# 08_-_FPGA_-_DDR3.net
KiCad netlist of a schematic drawn in Altium Designer
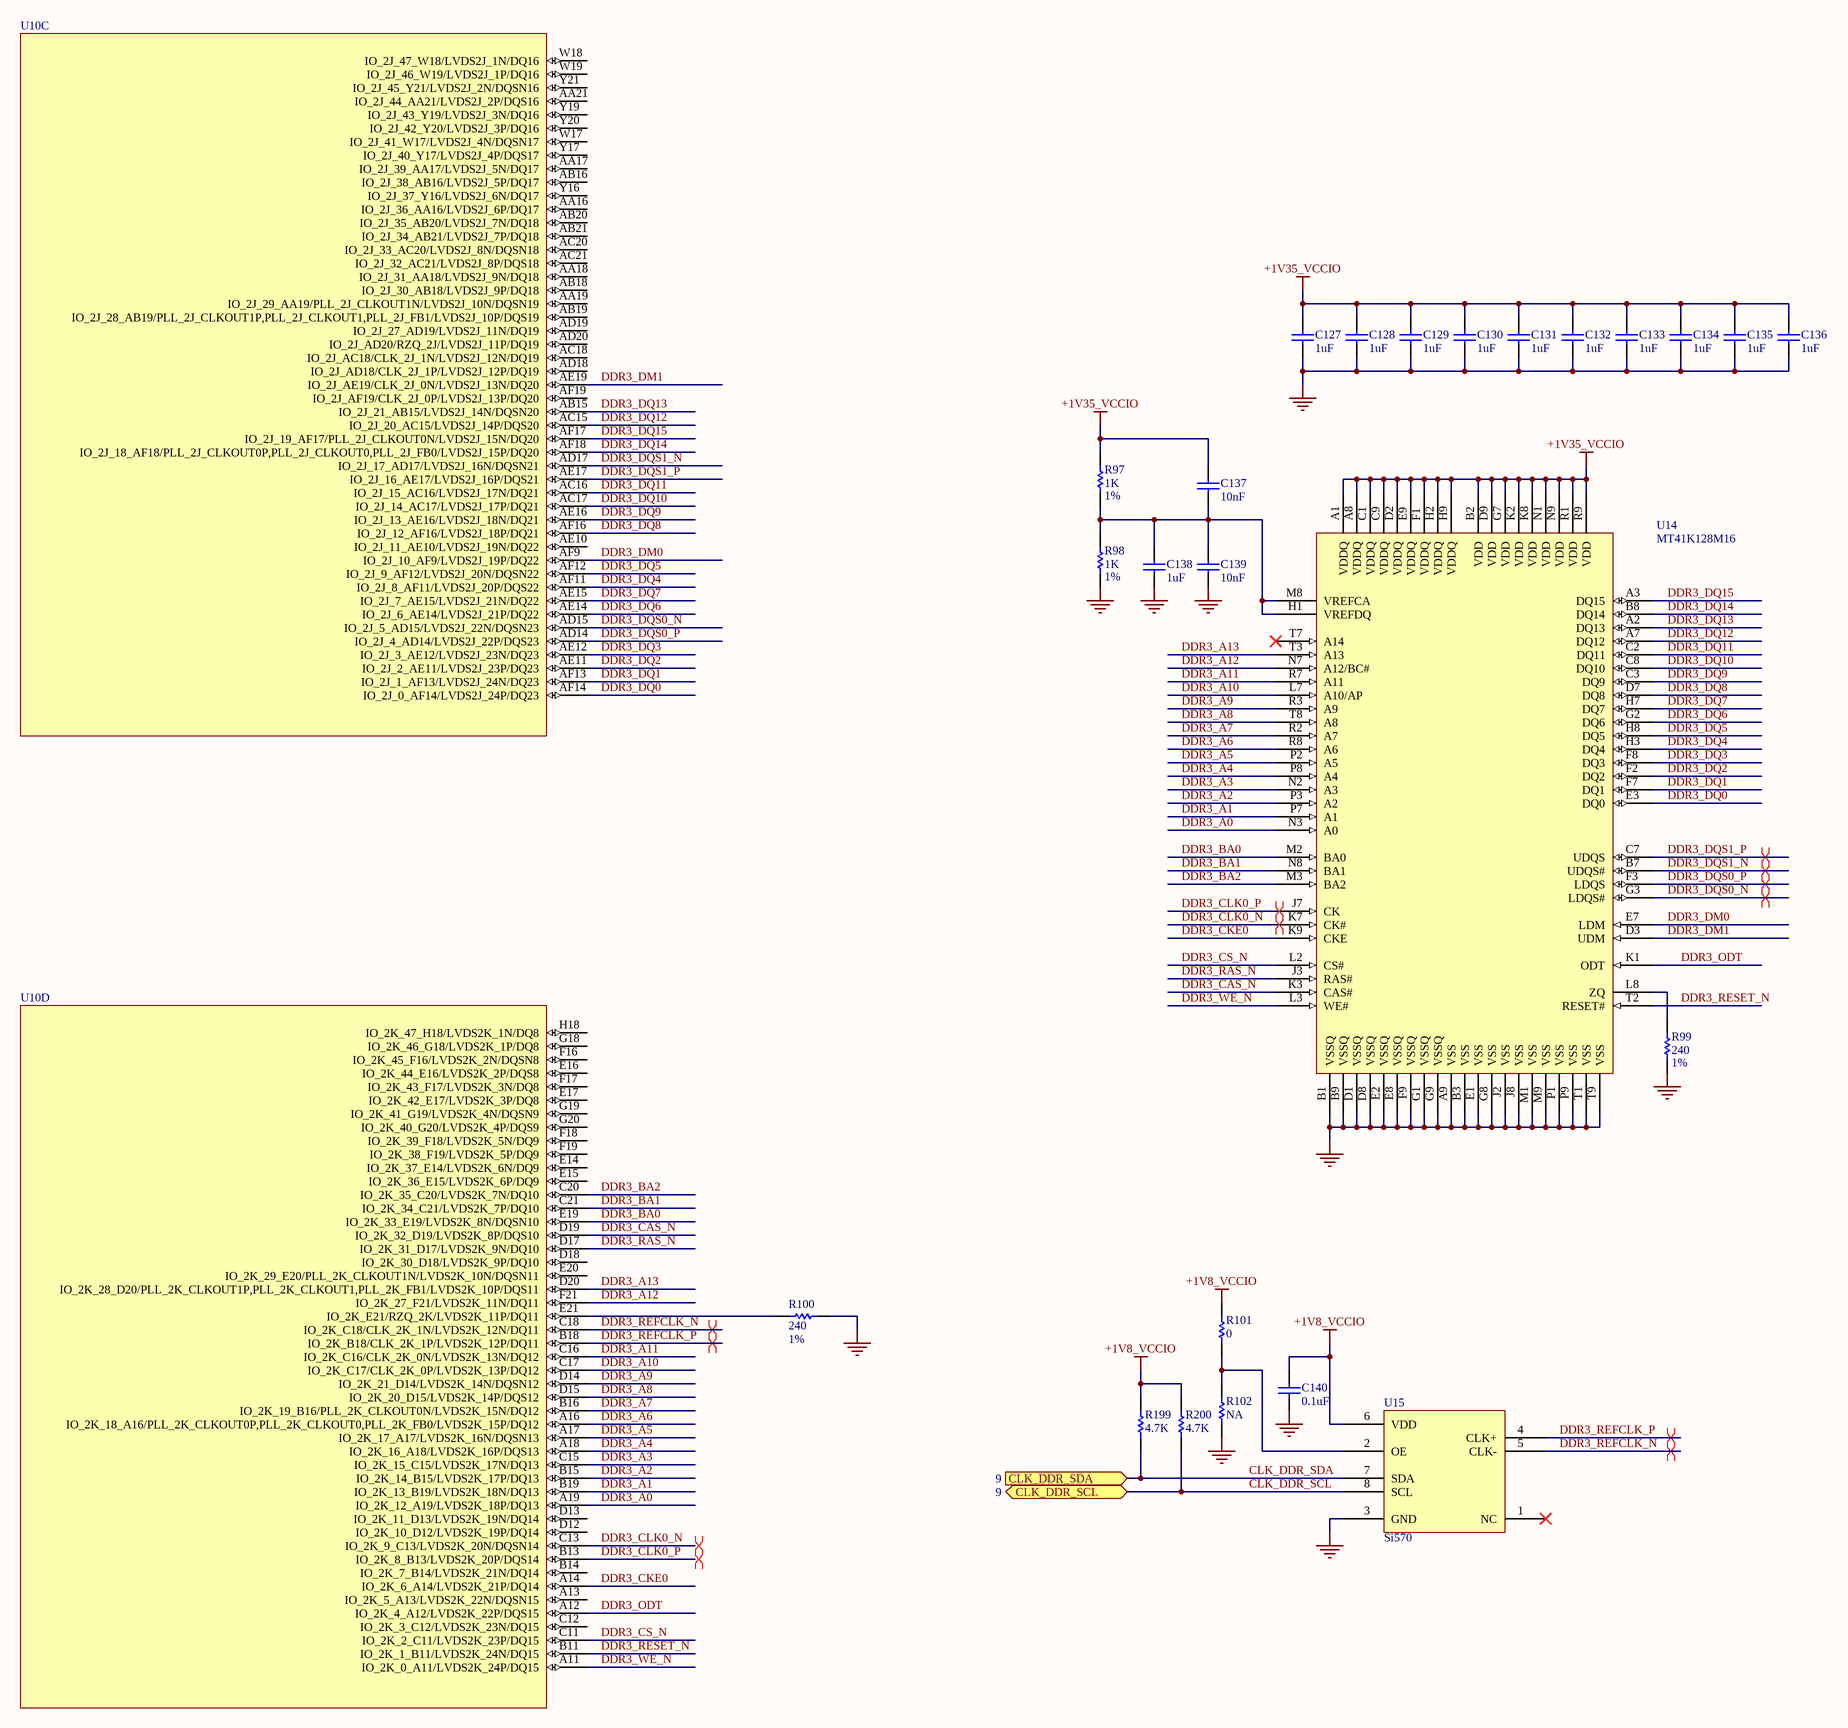
[diagram p0: [08] - FPGA - DDR3.SchDoc]

(export (version "E")
  (design (tool "Eeschema 10.0.6"))
  (components
    (comp (ref "C127")
      (value "1uF")
      (footprint "0402_C")
      (description "Non-Pol SMD Capacitor")
      (fields (field (name "MANUFACTURER PART NUM") "GRM155R70J105KA12"))
      (libsource (lib "Passive Components") (part "Cap SMD"))
    )
    (comp (ref "C128")
      (value "1uF")
      (footprint "0402_C")
      (description "Non-Pol SMD Capacitor")
      (fields (field (name "MANUFACTURER PART NUM") "GRM155R70J105KA12"))
      (libsource (lib "Passive Components") (part "Cap SMD"))
    )
    (comp (ref "C129")
      (value "1uF")
      (footprint "0402_C")
      (description "Non-Pol SMD Capacitor")
      (fields (field (name "MANUFACTURER PART NUM") "GRM155R70J105KA12"))
      (libsource (lib "Passive Components") (part "Cap SMD"))
    )
    (comp (ref "C130")
      (value "1uF")
      (footprint "0402_C")
      (description "Non-Pol SMD Capacitor")
      (fields (field (name "MANUFACTURER PART NUM") "GRM155R70J105KA12"))
      (libsource (lib "Passive Components") (part "Cap SMD"))
    )
    (comp (ref "C131")
      (value "1uF")
      (footprint "0402_C")
      (description "Non-Pol SMD Capacitor")
      (fields (field (name "MANUFACTURER PART NUM") "GRM155R70J105KA12"))
      (libsource (lib "Passive Components") (part "Cap SMD"))
    )
    (comp (ref "C132")
      (value "1uF")
      (footprint "0402_C")
      (description "Non-Pol SMD Capacitor")
      (fields (field (name "MANUFACTURER PART NUM") "GRM155R70J105KA12"))
      (libsource (lib "Passive Components") (part "Cap SMD"))
    )
    (comp (ref "C133")
      (value "1uF")
      (footprint "0402_C")
      (description "Non-Pol SMD Capacitor")
      (fields (field (name "MANUFACTURER PART NUM") "GRM155R70J105KA12"))
      (libsource (lib "Passive Components") (part "Cap SMD"))
    )
    (comp (ref "C134")
      (value "1uF")
      (footprint "0402_C")
      (description "Non-Pol SMD Capacitor")
      (fields (field (name "MANUFACTURER PART NUM") "GRM155R70J105KA12"))
      (libsource (lib "Passive Components") (part "Cap SMD"))
    )
    (comp (ref "C135")
      (value "1uF")
      (footprint "0402_C")
      (description "Non-Pol SMD Capacitor")
      (fields (field (name "MANUFACTURER PART NUM") "GRM155R70J105KA12"))
      (libsource (lib "Passive Components") (part "Cap SMD"))
    )
    (comp (ref "C136")
      (value "1uF")
      (footprint "0402_C")
      (description "Non-Pol SMD Capacitor")
      (fields (field (name "MANUFACTURER PART NUM") "GRM155R70J105KA12"))
      (libsource (lib "Passive Components") (part "Cap SMD"))
    )
    (comp (ref "C137")
      (value "10nF")
      (footprint "0402_C")
      (description "Non-Pol SMD Capacitor")
      (libsource (lib "Passive Components") (part "Cap SMD"))
    )
    (comp (ref "C138")
      (value "1uF")
      (footprint "0805_C")
      (description "Non-Pol SMD Capacitor")
      (libsource (lib "Passive Components") (part "Cap SMD"))
    )
    (comp (ref "C139")
      (value "10nF")
      (footprint "0402_C")
      (description "Non-Pol SMD Capacitor")
      (libsource (lib "Passive Components") (part "Cap SMD"))
    )
    (comp (ref "C140")
      (value "0.1uF")
      (footprint "0402_C")
      (description "Non-Pol SMD Capacitor")
      (libsource (lib "Passive Components") (part "Cap SMD"))
    )
    (comp (ref "R97")
      (value "1K")
      (footprint "0402_R")
      (description "SMD Resistor")
      (fields (field (name "TOLERANCE") "1%"))
      (libsource (lib "Passive Components") (part "Res SMD"))
    )
    (comp (ref "R98")
      (value "1K")
      (footprint "0402_R")
      (description "SMD Resistor")
      (fields (field (name "TOLERANCE") "1%"))
      (libsource (lib "Passive Components") (part "Res SMD"))
    )
    (comp (ref "R99")
      (value "240")
      (footprint "0402_R")
      (description "SMD Resistor")
      (fields (field (name "TOLERANCE") "1%"))
      (libsource (lib "Passive Components") (part "Res SMD"))
    )
    (comp (ref "R100")
      (value "240")
      (footprint "0402_R")
      (description "SMD Resistor")
      (fields (field (name "TOLERANCE") "1%"))
      (libsource (lib "Passive Components") (part "Res SMD"))
    )
    (comp (ref "R101")
      (value "0")
      (footprint "0402_R")
      (description "SMD Resistor")
      (fields (field (name "TOLERANCE") "5%"))
      (libsource (lib "Passive Components") (part "Res SMD"))
    )
    (comp (ref "R102")
      (value "NA")
      (footprint "0402_R")
      (description "SMD Resistor")
      (fields (field (name "TOLERANCE") "5%"))
      (libsource (lib "Passive Components") (part "Res SMD"))
    )
    (comp (ref "R199")
      (value "4.7K")
      (footprint "0402_R")
      (description "SMD Resistor")
      (fields (field (name "TOLERANCE") "5%"))
      (libsource (lib "Passive Components") (part "Res SMD"))
    )
    (comp (ref "R200")
      (value "4.7K")
      (footprint "0402_R")
      (description "SMD Resistor")
      (fields (field (name "TOLERANCE") "5%"))
      (libsource (lib "Passive Components") (part "Res SMD"))
    )
    (comp (ref "U10") (value "10AX016 F27") (footprint "FBGA672") (libsource (lib "") (part "10AX016_1")))
    (comp (ref "U14")
      (value "MT41K128M16")
      (footprint "FBGA96")
      (description "2Gb: x16 DDR3 SDRAM")
      (fields (field (name "MANUFACTURER PART NUM") "MT41K128M16JT-125"))
      (libsource (lib "Project_schlib") (part "MT41K128M16JT"))
    )
    (comp (ref "U15")
      (value "Si570")
      (description "10 MHZ TO 1.4 GHZ I2C PROGRAMMABLE XO/VCXO")
      (libsource (lib "Project_schlib") (part "Si570"))
    )
  )
  (nets
    (net (code "1") (name "+1V8_VCCIO") (class "Default")
      (node (ref "C140") (pin "1") (pinfunction "1_1") (pintype "passive"))
      (node (ref "R101") (pin "2") (pinfunction "2_2") (pintype "passive"))
      (node (ref "R199") (pin "2") (pinfunction "2_2") (pintype "passive"))
      (node (ref "R200") (pin "2") (pinfunction "2_2") (pintype "passive"))
      (node (ref "U15") (pin "6") (pinfunction "VDD_6") (pintype "power_in"))
    )
    (net (code "2") (name "+1V35_VCCIO") (class "Default")
      (node (ref "C127") (pin "2") (pinfunction "2_2") (pintype "passive"))
      (node (ref "C128") (pin "2") (pinfunction "2_2") (pintype "passive"))
      (node (ref "C129") (pin "2") (pinfunction "2_2") (pintype "passive"))
      (node (ref "C130") (pin "2") (pinfunction "2_2") (pintype "passive"))
      (node (ref "C131") (pin "2") (pinfunction "2_2") (pintype "passive"))
      (node (ref "C132") (pin "2") (pinfunction "2_2") (pintype "passive"))
      (node (ref "C133") (pin "2") (pinfunction "2_2") (pintype "passive"))
      (node (ref "C134") (pin "2") (pinfunction "2_2") (pintype "passive"))
      (node (ref "C135") (pin "2") (pinfunction "2_2") (pintype "passive"))
      (node (ref "C136") (pin "2") (pinfunction "2_2") (pintype "passive"))
      (node (ref "C137") (pin "2") (pinfunction "2_2") (pintype "passive"))
      (node (ref "R97") (pin "2") (pinfunction "2_2") (pintype "passive"))
      (node (ref "U14") (pin "A1") (pinfunction "VDDQ_A1") (pintype "power_in"))
      (node (ref "U14") (pin "A8") (pinfunction "VDDQ_A8") (pintype "power_in"))
      (node (ref "U14") (pin "B2") (pinfunction "VDD_B2") (pintype "power_in"))
      (node (ref "U14") (pin "C1") (pinfunction "VDDQ_C1") (pintype "power_in"))
      (node (ref "U14") (pin "C9") (pinfunction "VDDQ_C9") (pintype "power_in"))
      (node (ref "U14") (pin "D2") (pinfunction "VDDQ_D2") (pintype "power_in"))
      (node (ref "U14") (pin "D9") (pinfunction "VDD_D9") (pintype "power_in"))
      (node (ref "U14") (pin "E9") (pinfunction "VDDQ_E9") (pintype "power_in"))
      (node (ref "U14") (pin "F1") (pinfunction "VDDQ_F1") (pintype "power_in"))
      (node (ref "U14") (pin "G7") (pinfunction "VDD_G7") (pintype "power_in"))
      (node (ref "U14") (pin "H2") (pinfunction "VDDQ_H2") (pintype "power_in"))
      (node (ref "U14") (pin "H9") (pinfunction "VDDQ_H9") (pintype "power_in"))
      (node (ref "U14") (pin "K2") (pinfunction "VDD_K2") (pintype "power_in"))
      (node (ref "U14") (pin "K8") (pinfunction "VDD_K8") (pintype "power_in"))
      (node (ref "U14") (pin "N1") (pinfunction "VDD_N1") (pintype "power_in"))
      (node (ref "U14") (pin "N9") (pinfunction "VDD_N9") (pintype "power_in"))
      (node (ref "U14") (pin "R1") (pinfunction "VDD_R1") (pintype "power_in"))
      (node (ref "U14") (pin "R9") (pinfunction "VDD_R9") (pintype "power_in"))
    )
    (net (code "3") (name "/CLK_DDR_SCL") (class "Default")
      (node (ref "R200") (pin "1") (pinfunction "1_1") (pintype "passive"))
      (node (ref "U15") (pin "8") (pinfunction "SCL_8") (pintype "passive"))
    )
    (net (code "4") (name "/CLK_DDR_SDA") (class "Default")
      (node (ref "R199") (pin "1") (pinfunction "1_1") (pintype "passive"))
      (node (ref "U15") (pin "7") (pinfunction "SDA_7") (pintype "passive"))
    )
    (net (code "5") (name "/DDR3_A0") (class "Default")
      (node (ref "U10") (pin "A19") (pinfunction "IO_2K_12_A19/LVDS2K_18P/DQ13_A19") (pintype "bidirectional"))
      (node (ref "U14") (pin "N3") (pinfunction "A0_N3") (pintype "input"))
    )
    (net (code "6") (name "/DDR3_A1") (class "Default")
      (node (ref "U10") (pin "B19") (pinfunction "IO_2K_13_B19/LVDS2K_18N/DQ13_B19") (pintype "bidirectional"))
      (node (ref "U14") (pin "P7") (pinfunction "A1_P7") (pintype "input"))
    )
    (net (code "7") (name "/DDR3_A2") (class "Default")
      (node (ref "U10") (pin "B15") (pinfunction "IO_2K_14_B15/LVDS2K_17P/DQ13_B15") (pintype "bidirectional"))
      (node (ref "U14") (pin "P3") (pinfunction "A2_P3") (pintype "input"))
    )
    (net (code "8") (name "/DDR3_A3") (class "Default")
      (node (ref "U10") (pin "C15") (pinfunction "IO_2K_15_C15/LVDS2K_17N/DQ13_C15") (pintype "bidirectional"))
      (node (ref "U14") (pin "N2") (pinfunction "A3_N2") (pintype "input"))
    )
    (net (code "9") (name "/DDR3_A4") (class "Default")
      (node (ref "U10") (pin "A18") (pinfunction "IO_2K_16_A18/LVDS2K_16P/DQS13_A18") (pintype "bidirectional"))
      (node (ref "U14") (pin "P8") (pinfunction "A4_P8") (pintype "input"))
    )
    (net (code "10") (name "/DDR3_A5") (class "Default")
      (node (ref "U10") (pin "A17") (pinfunction "IO_2K_17_A17/LVDS2K_16N/DQSN13_A17") (pintype "bidirectional"))
      (node (ref "U14") (pin "P2") (pinfunction "A5_P2") (pintype "input"))
    )
    (net (code "11") (name "/DDR3_A6") (class "Default")
      (node (ref "U10") (pin "A16") (pinfunction "IO_2K_18_A16/PLL_2K_CLKOUT0P,PLL_2K_CLKOUT0,PLL_2K_FB0/LVDS2K_15P/DQ12_A16") (pintype "bidirectional"))
      (node (ref "U14") (pin "R8") (pinfunction "A6_R8") (pintype "input"))
    )
    (net (code "12") (name "/DDR3_A7") (class "Default")
      (node (ref "U10") (pin "B16") (pinfunction "IO_2K_19_B16/PLL_2K_CLKOUT0N/LVDS2K_15N/DQ12_B16") (pintype "bidirectional"))
      (node (ref "U14") (pin "R2") (pinfunction "A7_R2") (pintype "input"))
    )
    (net (code "13") (name "/DDR3_A8") (class "Default")
      (node (ref "U10") (pin "D15") (pinfunction "IO_2K_20_D15/LVDS2K_14P/DQS12_D15") (pintype "bidirectional"))
      (node (ref "U14") (pin "T8") (pinfunction "A8_T8") (pintype "input"))
    )
    (net (code "14") (name "/DDR3_A9") (class "Default")
      (node (ref "U10") (pin "D14") (pinfunction "IO_2K_21_D14/LVDS2K_14N/DQSN12_D14") (pintype "bidirectional"))
      (node (ref "U14") (pin "R3") (pinfunction "A9_R3") (pintype "input"))
    )
    (net (code "15") (name "/DDR3_A10") (class "Default")
      (node (ref "U10") (pin "C17") (pinfunction "IO_2K_C17/CLK_2K_0P/LVDS2K_13P/DQ12_C17") (pintype "bidirectional"))
      (node (ref "U14") (pin "L7") (pinfunction "A10/AP_L7") (pintype "input"))
    )
    (net (code "16") (name "/DDR3_A11") (class "Default")
      (node (ref "U10") (pin "C16") (pinfunction "IO_2K_C16/CLK_2K_0N/LVDS2K_13N/DQ12_C16") (pintype "bidirectional"))
      (node (ref "U14") (pin "R7") (pinfunction "A11_R7") (pintype "input"))
    )
    (net (code "17") (name "/DDR3_A12") (class "Default")
      (node (ref "U10") (pin "F21") (pinfunction "IO_2K_27_F21/LVDS2K_11N/DQ11_F21") (pintype "bidirectional"))
      (node (ref "U14") (pin "N7") (pinfunction "A12/BC#_N7") (pintype "input"))
    )
    (net (code "18") (name "/DDR3_A13") (class "Default")
      (node (ref "U10") (pin "D20") (pinfunction "IO_2K_28_D20/PLL_2K_CLKOUT1P,PLL_2K_CLKOUT1,PLL_2K_FB1/LVDS2K_10P/DQS11_D20") (pintype "bidirectional"))
      (node (ref "U14") (pin "T3") (pinfunction "A13_T3") (pintype "input"))
    )
    (net (code "19") (name "/DDR3_BA0") (class "Default")
      (node (ref "U10") (pin "E19") (pinfunction "IO_2K_33_E19/LVDS2K_8N/DQSN10_E19") (pintype "bidirectional"))
      (node (ref "U14") (pin "M2") (pinfunction "BA0_M2") (pintype "input"))
    )
    (net (code "20") (name "/DDR3_BA1") (class "Default")
      (node (ref "U10") (pin "C21") (pinfunction "IO_2K_34_C21/LVDS2K_7P/DQ10_C21") (pintype "bidirectional"))
      (node (ref "U14") (pin "N8") (pinfunction "BA1_N8") (pintype "input"))
    )
    (net (code "21") (name "/DDR3_BA2") (class "Default")
      (node (ref "U10") (pin "C20") (pinfunction "IO_2K_35_C20/LVDS2K_7N/DQ10_C20") (pintype "bidirectional"))
      (node (ref "U14") (pin "M3") (pinfunction "BA2_M3") (pintype "input"))
    )
    (net (code "22") (name "/DDR3_CAS_N") (class "Default")
      (node (ref "U10") (pin "D19") (pinfunction "IO_2K_32_D19/LVDS2K_8P/DQS10_D19") (pintype "bidirectional"))
      (node (ref "U14") (pin "K3") (pinfunction "CAS#_K3") (pintype "input"))
    )
    (net (code "23") (name "/DDR3_CKE0") (class "Default")
      (node (ref "U10") (pin "A14") (pinfunction "IO_2K_6_A14/LVDS2K_21P/DQ14_A14") (pintype "bidirectional"))
      (node (ref "U14") (pin "K9") (pinfunction "CKE_K9") (pintype "input"))
    )
    (net (code "24") (name "/DDR3_CLK0_N") (class "Default")
      (node (ref "U10") (pin "C13") (pinfunction "IO_2K_9_C13/LVDS2K_20N/DQSN14_C13") (pintype "bidirectional"))
      (node (ref "U14") (pin "K7") (pinfunction "CK#_K7") (pintype "input"))
    )
    (net (code "25") (name "/DDR3_CLK0_P") (class "Default")
      (node (ref "U10") (pin "B13") (pinfunction "IO_2K_8_B13/LVDS2K_20P/DQS14_B13") (pintype "bidirectional"))
      (node (ref "U14") (pin "J7") (pinfunction "CK_J7") (pintype "input"))
    )
    (net (code "26") (name "/DDR3_CS_N") (class "Default")
      (node (ref "U10") (pin "C11") (pinfunction "IO_2K_2_C11/LVDS2K_23P/DQ15_C11") (pintype "bidirectional"))
      (node (ref "U14") (pin "L2") (pinfunction "CS#_L2") (pintype "input"))
    )
    (net (code "27") (name "/DDR3_DM0") (class "Default")
      (node (ref "U10") (pin "AF9") (pinfunction "IO_2J_10_AF9/LVDS2J_19P/DQ22_AF9") (pintype "bidirectional"))
      (node (ref "U14") (pin "E7") (pinfunction "LDM_E7") (pintype "input"))
    )
    (net (code "28") (name "/DDR3_DM1") (class "Default")
      (node (ref "U10") (pin "AE19") (pinfunction "IO_2J_AE19/CLK_2J_0N/LVDS2J_13N/DQ20_AE19") (pintype "bidirectional"))
      (node (ref "U14") (pin "D3") (pinfunction "UDM_D3") (pintype "input"))
    )
    (net (code "29") (name "/DDR3_DQ0") (class "Default")
      (node (ref "U10") (pin "AF14") (pinfunction "IO_2J_0_AF14/LVDS2J_24P/DQ23_AF14") (pintype "bidirectional"))
      (node (ref "U14") (pin "E3") (pinfunction "DQ0_E3") (pintype "bidirectional"))
    )
    (net (code "30") (name "/DDR3_DQ1") (class "Default")
      (node (ref "U10") (pin "AF13") (pinfunction "IO_2J_1_AF13/LVDS2J_24N/DQ23_AF13") (pintype "bidirectional"))
      (node (ref "U14") (pin "F7") (pinfunction "DQ1_F7") (pintype "bidirectional"))
    )
    (net (code "31") (name "/DDR3_DQ2") (class "Default")
      (node (ref "U10") (pin "AE11") (pinfunction "IO_2J_2_AE11/LVDS2J_23P/DQ23_AE11") (pintype "bidirectional"))
      (node (ref "U14") (pin "F2") (pinfunction "DQ2_F2") (pintype "bidirectional"))
    )
    (net (code "32") (name "/DDR3_DQ3") (class "Default")
      (node (ref "U10") (pin "AE12") (pinfunction "IO_2J_3_AE12/LVDS2J_23N/DQ23_AE12") (pintype "bidirectional"))
      (node (ref "U14") (pin "F8") (pinfunction "DQ3_F8") (pintype "bidirectional"))
    )
    (net (code "33") (name "/DDR3_DQ4") (class "Default")
      (node (ref "U10") (pin "AF11") (pinfunction "IO_2J_8_AF11/LVDS2J_20P/DQS22_AF11") (pintype "bidirectional"))
      (node (ref "U14") (pin "H3") (pinfunction "DQ4_H3") (pintype "bidirectional"))
    )
    (net (code "34") (name "/DDR3_DQ5") (class "Default")
      (node (ref "U10") (pin "AF12") (pinfunction "IO_2J_9_AF12/LVDS2J_20N/DQSN22_AF12") (pintype "bidirectional"))
      (node (ref "U14") (pin "H8") (pinfunction "DQ5_H8") (pintype "bidirectional"))
    )
    (net (code "35") (name "/DDR3_DQ6") (class "Default")
      (node (ref "U10") (pin "AE14") (pinfunction "IO_2J_6_AE14/LVDS2J_21P/DQ22_AE14") (pintype "bidirectional"))
      (node (ref "U14") (pin "G2") (pinfunction "DQ6_G2") (pintype "bidirectional"))
    )
    (net (code "36") (name "/DDR3_DQ7") (class "Default")
      (node (ref "U10") (pin "AE15") (pinfunction "IO_2J_7_AE15/LVDS2J_21N/DQ22_AE15") (pintype "bidirectional"))
      (node (ref "U14") (pin "H7") (pinfunction "DQ7_H7") (pintype "bidirectional"))
    )
    (net (code "37") (name "/DDR3_DQ8") (class "Default")
      (node (ref "U10") (pin "AF16") (pinfunction "IO_2J_12_AF16/LVDS2J_18P/DQ21_AF16") (pintype "bidirectional"))
      (node (ref "U14") (pin "D7") (pinfunction "DQ8_D7") (pintype "bidirectional"))
    )
    (net (code "38") (name "/DDR3_DQ9") (class "Default")
      (node (ref "U10") (pin "AE16") (pinfunction "IO_2J_13_AE16/LVDS2J_18N/DQ21_AE16") (pintype "bidirectional"))
      (node (ref "U14") (pin "C3") (pinfunction "DQ9_C3") (pintype "bidirectional"))
    )
    (net (code "39") (name "/DDR3_DQ10") (class "Default")
      (node (ref "U10") (pin "AC17") (pinfunction "IO_2J_14_AC17/LVDS2J_17P/DQ21_AC17") (pintype "bidirectional"))
      (node (ref "U14") (pin "C8") (pinfunction "DQ10_C8") (pintype "bidirectional"))
    )
    (net (code "40") (name "/DDR3_DQ11") (class "Default")
      (node (ref "U10") (pin "AC16") (pinfunction "IO_2J_15_AC16/LVDS2J_17N/DQ21_AC16") (pintype "bidirectional"))
      (node (ref "U14") (pin "C2") (pinfunction "DQ11_C2") (pintype "bidirectional"))
    )
    (net (code "41") (name "/DDR3_DQ12") (class "Default")
      (node (ref "U10") (pin "AC15") (pinfunction "IO_2J_20_AC15/LVDS2J_14P/DQS20_AC15") (pintype "bidirectional"))
      (node (ref "U14") (pin "A7") (pinfunction "DQ12_A7") (pintype "bidirectional"))
    )
    (net (code "42") (name "/DDR3_DQ13") (class "Default")
      (node (ref "U10") (pin "AB15") (pinfunction "IO_2J_21_AB15/LVDS2J_14N/DQSN20_AB15") (pintype "bidirectional"))
      (node (ref "U14") (pin "A2") (pinfunction "DQ13_A2") (pintype "bidirectional"))
    )
    (net (code "43") (name "/DDR3_DQ14") (class "Default")
      (node (ref "U10") (pin "AF18") (pinfunction "IO_2J_18_AF18/PLL_2J_CLKOUT0P,PLL_2J_CLKOUT0,PLL_2J_FB0/LVDS2J_15P/DQ20_AF18") (pintype "bidirectional"))
      (node (ref "U14") (pin "B8") (pinfunction "DQ14_B8") (pintype "bidirectional"))
    )
    (net (code "44") (name "/DDR3_DQ15") (class "Default")
      (node (ref "U10") (pin "AF17") (pinfunction "IO_2J_19_AF17/PLL_2J_CLKOUT0N/LVDS2J_15N/DQ20_AF17") (pintype "bidirectional"))
      (node (ref "U14") (pin "A3") (pinfunction "DQ15_A3") (pintype "bidirectional"))
    )
    (net (code "45") (name "/DDR3_DQS0_N") (class "Default")
      (node (ref "U10") (pin "AD15") (pinfunction "IO_2J_5_AD15/LVDS2J_22N/DQSN23_AD15") (pintype "bidirectional"))
      (node (ref "U14") (pin "G3") (pinfunction "LDQS#_G3") (pintype "bidirectional"))
    )
    (net (code "46") (name "/DDR3_DQS0_P") (class "Default")
      (node (ref "U10") (pin "AD14") (pinfunction "IO_2J_4_AD14/LVDS2J_22P/DQS23_AD14") (pintype "bidirectional"))
      (node (ref "U14") (pin "F3") (pinfunction "LDQS_F3") (pintype "bidirectional"))
    )
    (net (code "47") (name "/DDR3_DQS1_N") (class "Default")
      (node (ref "U10") (pin "AD17") (pinfunction "IO_2J_17_AD17/LVDS2J_16N/DQSN21_AD17") (pintype "bidirectional"))
      (node (ref "U14") (pin "B7") (pinfunction "UDQS#_B7") (pintype "bidirectional"))
    )
    (net (code "48") (name "/DDR3_DQS1_P") (class "Default")
      (node (ref "U10") (pin "AE17") (pinfunction "IO_2J_16_AE17/LVDS2J_16P/DQS21_AE17") (pintype "bidirectional"))
      (node (ref "U14") (pin "C7") (pinfunction "UDQS_C7") (pintype "bidirectional"))
    )
    (net (code "49") (name "/DDR3_ODT") (class "Default")
      (node (ref "U10") (pin "A12") (pinfunction "IO_2K_4_A12/LVDS2K_22P/DQS15_A12") (pintype "bidirectional"))
      (node (ref "U14") (pin "K1") (pinfunction "ODT_K1") (pintype "input"))
    )
    (net (code "50") (name "/DDR3_RAS_N") (class "Default")
      (node (ref "U10") (pin "D17") (pinfunction "IO_2K_31_D17/LVDS2K_9N/DQ10_D17") (pintype "bidirectional"))
      (node (ref "U14") (pin "J3") (pinfunction "RAS#_J3") (pintype "input"))
    )
    (net (code "51") (name "/DDR3_REFCLK_N") (class "Default")
      (node (ref "U10") (pin "C18") (pinfunction "IO_2K_C18/CLK_2K_1N/LVDS2K_12N/DQ11_C18") (pintype "bidirectional"))
      (node (ref "U15") (pin "5") (pinfunction "CLK-_5") (pintype "passive"))
    )
    (net (code "52") (name "/DDR3_REFCLK_P") (class "Default")
      (node (ref "U10") (pin "B18") (pinfunction "IO_2K_B18/CLK_2K_1P/LVDS2K_12P/DQ11_B18") (pintype "bidirectional"))
      (node (ref "U15") (pin "4") (pinfunction "CLK+_4") (pintype "passive"))
    )
    (net (code "53") (name "/DDR3_RESET_N") (class "Default")
      (node (ref "U10") (pin "B11") (pinfunction "IO_2K_1_B11/LVDS2K_24N/DQ15_B11") (pintype "bidirectional"))
      (node (ref "U14") (pin "T2") (pinfunction "RESET#_T2") (pintype "input"))
    )
    (net (code "54") (name "/DDR3_WE_N") (class "Default")
      (node (ref "U10") (pin "A11") (pinfunction "IO_2K_0_A11/LVDS2K_24P/DQ15_A11") (pintype "bidirectional"))
      (node (ref "U14") (pin "L3") (pinfunction "WE#_L3") (pintype "input"))
    )
    (net (code "55") (name "GND") (class "Default")
      (node (ref "C127") (pin "1") (pinfunction "1_1") (pintype "passive"))
      (node (ref "C128") (pin "1") (pinfunction "1_1") (pintype "passive"))
      (node (ref "C129") (pin "1") (pinfunction "1_1") (pintype "passive"))
      (node (ref "C130") (pin "1") (pinfunction "1_1") (pintype "passive"))
      (node (ref "C131") (pin "1") (pinfunction "1_1") (pintype "passive"))
      (node (ref "C132") (pin "1") (pinfunction "1_1") (pintype "passive"))
      (node (ref "C133") (pin "1") (pinfunction "1_1") (pintype "passive"))
      (node (ref "C134") (pin "1") (pinfunction "1_1") (pintype "passive"))
      (node (ref "C135") (pin "1") (pinfunction "1_1") (pintype "passive"))
      (node (ref "C136") (pin "1") (pinfunction "1_1") (pintype "passive"))
      (node (ref "C138") (pin "1") (pinfunction "1_1") (pintype "passive"))
      (node (ref "C139") (pin "1") (pinfunction "1_1") (pintype "passive"))
      (node (ref "C140") (pin "2") (pinfunction "2_2") (pintype "passive"))
      (node (ref "R100") (pin "1") (pinfunction "1_1") (pintype "passive"))
      (node (ref "R102") (pin "1") (pinfunction "1_1") (pintype "passive"))
      (node (ref "R98") (pin "1") (pinfunction "1_1") (pintype "passive"))
      (node (ref "R99") (pin "1") (pinfunction "1_1") (pintype "passive"))
      (node (ref "U14") (pin "A9") (pinfunction "VSS_A9") (pintype "power_in"))
      (node (ref "U14") (pin "B1") (pinfunction "VSSQ_B1") (pintype "power_in"))
      (node (ref "U14") (pin "B3") (pinfunction "VSS_B3") (pintype "power_in"))
      (node (ref "U14") (pin "B9") (pinfunction "VSSQ_B9") (pintype "power_in"))
      (node (ref "U14") (pin "D1") (pinfunction "VSSQ_D1") (pintype "power_in"))
      (node (ref "U14") (pin "D8") (pinfunction "VSSQ_D8") (pintype "power_in"))
      (node (ref "U14") (pin "E1") (pinfunction "VSS_E1") (pintype "power_in"))
      (node (ref "U14") (pin "E2") (pinfunction "VSSQ_E2") (pintype "power_in"))
      (node (ref "U14") (pin "E8") (pinfunction "VSSQ_E8") (pintype "power_in"))
      (node (ref "U14") (pin "F9") (pinfunction "VSSQ_F9") (pintype "power_in"))
      (node (ref "U14") (pin "G1") (pinfunction "VSSQ_G1") (pintype "power_in"))
      (node (ref "U14") (pin "G8") (pinfunction "VSS_G8") (pintype "power_in"))
      (node (ref "U14") (pin "G9") (pinfunction "VSSQ_G9") (pintype "power_in"))
      (node (ref "U14") (pin "J2") (pinfunction "VSS_J2") (pintype "power_in"))
      (node (ref "U14") (pin "J8") (pinfunction "VSS_J8") (pintype "power_in"))
      (node (ref "U14") (pin "M1") (pinfunction "VSS_M1") (pintype "power_in"))
      (node (ref "U14") (pin "M9") (pinfunction "VSS_M9") (pintype "power_in"))
      (node (ref "U14") (pin "P1") (pinfunction "VSS_P1") (pintype "power_in"))
      (node (ref "U14") (pin "P9") (pinfunction "VSS_P9") (pintype "power_in"))
      (node (ref "U14") (pin "T1") (pinfunction "VSS_T1") (pintype "power_in"))
      (node (ref "U14") (pin "T9") (pinfunction "VSS_T9") (pintype "power_in"))
      (node (ref "U15") (pin "3") (pinfunction "GND_3") (pintype "power_in"))
    )
    (net (code "56") (name "Net-(U10D-IO_2K_E21{slash}RZQ_2K{slash}LVDS2K_11P{slash}DQ11)") (class "Default")
      (node (ref "R100") (pin "2") (pinfunction "2_2") (pintype "passive"))
      (node (ref "U10") (pin "E21") (pinfunction "IO_2K_E21/RZQ_2K/LVDS2K_11P/DQ11_E21") (pintype "bidirectional"))
    )
    (net (code "57") (name "Net-(U14-VREFCA)") (class "Default")
      (node (ref "C137") (pin "1") (pinfunction "1_1") (pintype "passive"))
      (node (ref "C138") (pin "2") (pinfunction "2_2") (pintype "passive"))
      (node (ref "C139") (pin "2") (pinfunction "2_2") (pintype "passive"))
      (node (ref "R97") (pin "1") (pinfunction "1_1") (pintype "passive"))
      (node (ref "R98") (pin "2") (pinfunction "2_2") (pintype "passive"))
      (node (ref "U14") (pin "H1") (pinfunction "VREFDQ_H1") (pintype "power_in"))
      (node (ref "U14") (pin "M8") (pinfunction "VREFCA_M8") (pintype "power_in"))
    )
    (net (code "58") (name "Net-(U14-ZQ)") (class "Default")
      (node (ref "R99") (pin "2") (pinfunction "2_2") (pintype "passive"))
      (node (ref "U14") (pin "L8") (pinfunction "ZQ_L8") (pintype "passive"))
    )
    (net (code "59") (name "Net-(U15-OE)") (class "Default")
      (node (ref "R101") (pin "1") (pinfunction "1_1") (pintype "passive"))
      (node (ref "R102") (pin "2") (pinfunction "2_2") (pintype "passive"))
      (node (ref "U15") (pin "2") (pinfunction "OE_2") (pintype "passive"))
    )
    (net (code "60") (name "unconnected-(U10C-IO_2J_11_AE10{slash}LVDS2J_19N{slash}DQ22-PadAE10)") (class "Default")
      (node (ref "U10") (pin "AE10") (pinfunction "IO_2J_11_AE10/LVDS2J_19N/DQ22_AE10") (pintype "bidirectional"))
    )
    (net (code "61") (name "unconnected-(U10C-IO_2J_27_AD19{slash}LVDS2J_11N{slash}DQ19-PadAD19)") (class "Default")
      (node (ref "U10") (pin "AD19") (pinfunction "IO_2J_27_AD19/LVDS2J_11N/DQ19_AD19") (pintype "bidirectional"))
    )
    (net (code "62") (name "unconnected-(U10C-IO_2J_28_AB19{slash}PLL_2J_CLKOUT1P,PLL_2J_CLKOUT1,PLL_2J_FB1{slash}LVDS2J_10P{slash}DQS19-PadAB19)") (class "Default")
      (node (ref "U10") (pin "AB19") (pinfunction "IO_2J_28_AB19/PLL_2J_CLKOUT1P,PLL_2J_CLKOUT1,PLL_2J_FB1/LVDS2J_10P/DQS19_AB19") (pintype "bidirectional"))
    )
    (net (code "63") (name "unconnected-(U10C-IO_2J_29_AA19{slash}PLL_2J_CLKOUT1N{slash}LVDS2J_10N{slash}DQSN19-PadAA19)") (class "Default")
      (node (ref "U10") (pin "AA19") (pinfunction "IO_2J_29_AA19/PLL_2J_CLKOUT1N/LVDS2J_10N/DQSN19_AA19") (pintype "bidirectional"))
    )
    (net (code "64") (name "unconnected-(U10C-IO_2J_30_AB18{slash}LVDS2J_9P{slash}DQ18-PadAB18)") (class "Default")
      (node (ref "U10") (pin "AB18") (pinfunction "IO_2J_30_AB18/LVDS2J_9P/DQ18_AB18") (pintype "bidirectional"))
    )
    (net (code "65") (name "unconnected-(U10C-IO_2J_31_AA18{slash}LVDS2J_9N{slash}DQ18-PadAA18)") (class "Default")
      (node (ref "U10") (pin "AA18") (pinfunction "IO_2J_31_AA18/LVDS2J_9N/DQ18_AA18") (pintype "bidirectional"))
    )
    (net (code "66") (name "unconnected-(U10C-IO_2J_32_AC21{slash}LVDS2J_8P{slash}DQS18-PadAC21)") (class "Default")
      (node (ref "U10") (pin "AC21") (pinfunction "IO_2J_32_AC21/LVDS2J_8P/DQS18_AC21") (pintype "bidirectional"))
    )
    (net (code "67") (name "unconnected-(U10C-IO_2J_33_AC20{slash}LVDS2J_8N{slash}DQSN18-PadAC20)") (class "Default")
      (node (ref "U10") (pin "AC20") (pinfunction "IO_2J_33_AC20/LVDS2J_8N/DQSN18_AC20") (pintype "bidirectional"))
    )
    (net (code "68") (name "unconnected-(U10C-IO_2J_34_AB21{slash}LVDS2J_7P{slash}DQ18-PadAB21)") (class "Default")
      (node (ref "U10") (pin "AB21") (pinfunction "IO_2J_34_AB21/LVDS2J_7P/DQ18_AB21") (pintype "bidirectional"))
    )
    (net (code "69") (name "unconnected-(U10C-IO_2J_35_AB20{slash}LVDS2J_7N{slash}DQ18-PadAB20)") (class "Default")
      (node (ref "U10") (pin "AB20") (pinfunction "IO_2J_35_AB20/LVDS2J_7N/DQ18_AB20") (pintype "bidirectional"))
    )
    (net (code "70") (name "unconnected-(U10C-IO_2J_36_AA16{slash}LVDS2J_6P{slash}DQ17-PadAA16)") (class "Default")
      (node (ref "U10") (pin "AA16") (pinfunction "IO_2J_36_AA16/LVDS2J_6P/DQ17_AA16") (pintype "bidirectional"))
    )
    (net (code "71") (name "unconnected-(U10C-IO_2J_37_Y16{slash}LVDS2J_6N{slash}DQ17-PadY16)") (class "Default")
      (node (ref "U10") (pin "Y16") (pinfunction "IO_2J_37_Y16/LVDS2J_6N/DQ17_Y16") (pintype "bidirectional"))
    )
    (net (code "72") (name "unconnected-(U10C-IO_2J_38_AB16{slash}LVDS2J_5P{slash}DQ17-PadAB16)") (class "Default")
      (node (ref "U10") (pin "AB16") (pinfunction "IO_2J_38_AB16/LVDS2J_5P/DQ17_AB16") (pintype "bidirectional"))
    )
    (net (code "73") (name "unconnected-(U10C-IO_2J_39_AA17{slash}LVDS2J_5N{slash}DQ17-PadAA17)") (class "Default")
      (node (ref "U10") (pin "AA17") (pinfunction "IO_2J_39_AA17/LVDS2J_5N/DQ17_AA17") (pintype "bidirectional"))
    )
    (net (code "74") (name "unconnected-(U10C-IO_2J_40_Y17{slash}LVDS2J_4P{slash}DQS17-PadY17)") (class "Default")
      (node (ref "U10") (pin "Y17") (pinfunction "IO_2J_40_Y17/LVDS2J_4P/DQS17_Y17") (pintype "bidirectional"))
    )
    (net (code "75") (name "unconnected-(U10C-IO_2J_41_W17{slash}LVDS2J_4N{slash}DQSN17-PadW17)") (class "Default")
      (node (ref "U10") (pin "W17") (pinfunction "IO_2J_41_W17/LVDS2J_4N/DQSN17_W17") (pintype "bidirectional"))
    )
    (net (code "76") (name "unconnected-(U10C-IO_2J_42_Y20{slash}LVDS2J_3P{slash}DQ16-PadY20)") (class "Default")
      (node (ref "U10") (pin "Y20") (pinfunction "IO_2J_42_Y20/LVDS2J_3P/DQ16_Y20") (pintype "bidirectional"))
    )
    (net (code "77") (name "unconnected-(U10C-IO_2J_43_Y19{slash}LVDS2J_3N{slash}DQ16-PadY19)") (class "Default")
      (node (ref "U10") (pin "Y19") (pinfunction "IO_2J_43_Y19/LVDS2J_3N/DQ16_Y19") (pintype "bidirectional"))
    )
    (net (code "78") (name "unconnected-(U10C-IO_2J_44_AA21{slash}LVDS2J_2P{slash}DQS16-PadAA21)") (class "Default")
      (node (ref "U10") (pin "AA21") (pinfunction "IO_2J_44_AA21/LVDS2J_2P/DQS16_AA21") (pintype "bidirectional"))
    )
    (net (code "79") (name "unconnected-(U10C-IO_2J_45_Y21{slash}LVDS2J_2N{slash}DQSN16-PadY21)") (class "Default")
      (node (ref "U10") (pin "Y21") (pinfunction "IO_2J_45_Y21/LVDS2J_2N/DQSN16_Y21") (pintype "bidirectional"))
    )
    (net (code "80") (name "unconnected-(U10C-IO_2J_46_W19{slash}LVDS2J_1P{slash}DQ16-PadW19)") (class "Default")
      (node (ref "U10") (pin "W19") (pinfunction "IO_2J_46_W19/LVDS2J_1P/DQ16_W19") (pintype "bidirectional"))
    )
    (net (code "81") (name "unconnected-(U10C-IO_2J_47_W18{slash}LVDS2J_1N{slash}DQ16-PadW18)") (class "Default")
      (node (ref "U10") (pin "W18") (pinfunction "IO_2J_47_W18/LVDS2J_1N/DQ16_W18") (pintype "bidirectional"))
    )
    (net (code "82") (name "unconnected-(U10C-IO_2J_AC18{slash}CLK_2J_1N{slash}LVDS2J_12N{slash}DQ19-PadAC18)") (class "Default")
      (node (ref "U10") (pin "AC18") (pinfunction "IO_2J_AC18/CLK_2J_1N/LVDS2J_12N/DQ19_AC18") (pintype "bidirectional"))
    )
    (net (code "83") (name "unconnected-(U10C-IO_2J_AD18{slash}CLK_2J_1P{slash}LVDS2J_12P{slash}DQ19-PadAD18)") (class "Default")
      (node (ref "U10") (pin "AD18") (pinfunction "IO_2J_AD18/CLK_2J_1P/LVDS2J_12P/DQ19_AD18") (pintype "bidirectional"))
    )
    (net (code "84") (name "unconnected-(U10C-IO_2J_AD20{slash}RZQ_2J{slash}LVDS2J_11P{slash}DQ19-PadAD20)") (class "Default")
      (node (ref "U10") (pin "AD20") (pinfunction "IO_2J_AD20/RZQ_2J/LVDS2J_11P/DQ19_AD20") (pintype "bidirectional"))
    )
    (net (code "85") (name "unconnected-(U10C-IO_2J_AF19{slash}CLK_2J_0P{slash}LVDS2J_13P{slash}DQ20-PadAF19)") (class "Default")
      (node (ref "U10") (pin "AF19") (pinfunction "IO_2J_AF19/CLK_2J_0P/LVDS2J_13P/DQ20_AF19") (pintype "bidirectional"))
    )
    (net (code "86") (name "unconnected-(U10D-IO_2K_3_C12{slash}LVDS2K_23N{slash}DQ15-PadC12)") (class "Default")
      (node (ref "U10") (pin "C12") (pinfunction "IO_2K_3_C12/LVDS2K_23N/DQ15_C12") (pintype "bidirectional"))
    )
    (net (code "87") (name "unconnected-(U10D-IO_2K_5_A13{slash}LVDS2K_22N{slash}DQSN15-PadA13)") (class "Default")
      (node (ref "U10") (pin "A13") (pinfunction "IO_2K_5_A13/LVDS2K_22N/DQSN15_A13") (pintype "bidirectional"))
    )
    (net (code "88") (name "unconnected-(U10D-IO_2K_7_B14{slash}LVDS2K_21N{slash}DQ14-PadB14)") (class "Default")
      (node (ref "U10") (pin "B14") (pinfunction "IO_2K_7_B14/LVDS2K_21N/DQ14_B14") (pintype "bidirectional"))
    )
    (net (code "89") (name "unconnected-(U10D-IO_2K_10_D12{slash}LVDS2K_19P{slash}DQ14-PadD12)") (class "Default")
      (node (ref "U10") (pin "D12") (pinfunction "IO_2K_10_D12/LVDS2K_19P/DQ14_D12") (pintype "bidirectional"))
    )
    (net (code "90") (name "unconnected-(U10D-IO_2K_11_D13{slash}LVDS2K_19N{slash}DQ14-PadD13)") (class "Default")
      (node (ref "U10") (pin "D13") (pinfunction "IO_2K_11_D13/LVDS2K_19N/DQ14_D13") (pintype "bidirectional"))
    )
    (net (code "91") (name "unconnected-(U10D-IO_2K_29_E20{slash}PLL_2K_CLKOUT1N{slash}LVDS2K_10N{slash}DQSN11-PadE20)") (class "Default")
      (node (ref "U10") (pin "E20") (pinfunction "IO_2K_29_E20/PLL_2K_CLKOUT1N/LVDS2K_10N/DQSN11_E20") (pintype "bidirectional"))
    )
    (net (code "92") (name "unconnected-(U10D-IO_2K_30_D18{slash}LVDS2K_9P{slash}DQ10-PadD18)") (class "Default")
      (node (ref "U10") (pin "D18") (pinfunction "IO_2K_30_D18/LVDS2K_9P/DQ10_D18") (pintype "bidirectional"))
    )
    (net (code "93") (name "unconnected-(U10D-IO_2K_36_E15{slash}LVDS2K_6P{slash}DQ9-PadE15)") (class "Default")
      (node (ref "U10") (pin "E15") (pinfunction "IO_2K_36_E15/LVDS2K_6P/DQ9_E15") (pintype "bidirectional"))
    )
    (net (code "94") (name "unconnected-(U10D-IO_2K_37_E14{slash}LVDS2K_6N{slash}DQ9-PadE14)") (class "Default")
      (node (ref "U10") (pin "E14") (pinfunction "IO_2K_37_E14/LVDS2K_6N/DQ9_E14") (pintype "bidirectional"))
    )
    (net (code "95") (name "unconnected-(U10D-IO_2K_38_F19{slash}LVDS2K_5P{slash}DQ9-PadF19)") (class "Default")
      (node (ref "U10") (pin "F19") (pinfunction "IO_2K_38_F19/LVDS2K_5P/DQ9_F19") (pintype "bidirectional"))
    )
    (net (code "96") (name "unconnected-(U10D-IO_2K_39_F18{slash}LVDS2K_5N{slash}DQ9-PadF18)") (class "Default")
      (node (ref "U10") (pin "F18") (pinfunction "IO_2K_39_F18/LVDS2K_5N/DQ9_F18") (pintype "bidirectional"))
    )
    (net (code "97") (name "unconnected-(U10D-IO_2K_40_G20{slash}LVDS2K_4P{slash}DQS9-PadG20)") (class "Default")
      (node (ref "U10") (pin "G20") (pinfunction "IO_2K_40_G20/LVDS2K_4P/DQS9_G20") (pintype "bidirectional"))
    )
    (net (code "98") (name "unconnected-(U10D-IO_2K_41_G19{slash}LVDS2K_4N{slash}DQSN9-PadG19)") (class "Default")
      (node (ref "U10") (pin "G19") (pinfunction "IO_2K_41_G19/LVDS2K_4N/DQSN9_G19") (pintype "bidirectional"))
    )
    (net (code "99") (name "unconnected-(U10D-IO_2K_42_E17{slash}LVDS2K_3P{slash}DQ8-PadE17)") (class "Default")
      (node (ref "U10") (pin "E17") (pinfunction "IO_2K_42_E17/LVDS2K_3P/DQ8_E17") (pintype "bidirectional"))
    )
    (net (code "100") (name "unconnected-(U10D-IO_2K_43_F17{slash}LVDS2K_3N{slash}DQ8-PadF17)") (class "Default")
      (node (ref "U10") (pin "F17") (pinfunction "IO_2K_43_F17/LVDS2K_3N/DQ8_F17") (pintype "bidirectional"))
    )
    (net (code "101") (name "unconnected-(U10D-IO_2K_44_E16{slash}LVDS2K_2P{slash}DQS8-PadE16)") (class "Default")
      (node (ref "U10") (pin "E16") (pinfunction "IO_2K_44_E16/LVDS2K_2P/DQS8_E16") (pintype "bidirectional"))
    )
    (net (code "102") (name "unconnected-(U10D-IO_2K_45_F16{slash}LVDS2K_2N{slash}DQSN8-PadF16)") (class "Default")
      (node (ref "U10") (pin "F16") (pinfunction "IO_2K_45_F16/LVDS2K_2N/DQSN8_F16") (pintype "bidirectional"))
    )
    (net (code "103") (name "unconnected-(U10D-IO_2K_46_G18{slash}LVDS2K_1P{slash}DQ8-PadG18)") (class "Default")
      (node (ref "U10") (pin "G18") (pinfunction "IO_2K_46_G18/LVDS2K_1P/DQ8_G18") (pintype "bidirectional"))
    )
    (net (code "104") (name "unconnected-(U10D-IO_2K_47_H18{slash}LVDS2K_1N{slash}DQ8-PadH18)") (class "Default")
      (node (ref "U10") (pin "H18") (pinfunction "IO_2K_47_H18/LVDS2K_1N/DQ8_H18") (pintype "bidirectional"))
    )
    (net (code "105") (name "unconnected-(U14-A14-PadT7)") (class "Default")
      (node (ref "U14") (pin "T7") (pinfunction "A14_T7") (pintype "input+no_connect"))
    )
    (net (code "106") (name "unconnected-(U15-NC-Pad1)") (class "Default")
      (node (ref "U15") (pin "1") (pinfunction "NC_1") (pintype "passive+no_connect"))
    )
  )
)
